# damper.net
KiCad netlist of a schematic drawn in EAGLE
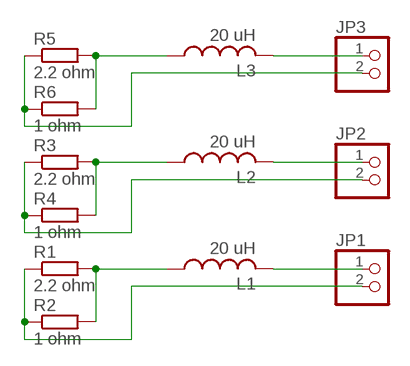
[diagram p0: schematic, sheet 1]

(export (version "E")
  (design (tool "Eeschema 10.0.6"))
  (components
    (comp (ref "JP1")
      (value "PINHD-1X2")
      (footprint "eagle-import:1X02")
      (libsource (lib "eagle-import") (part "PINHD-1X2"))
    )
    (comp (ref "JP2")
      (value "PINHD-1X2")
      (footprint "eagle-import:1X02")
      (libsource (lib "eagle-import") (part "PINHD-1X2"))
    )
    (comp (ref "JP3")
      (value "PINHD-1X2")
      (footprint "eagle-import:1X02")
      (libsource (lib "eagle-import") (part "PINHD-1X2"))
    )
    (comp (ref "L1")
      (value "20 uH")
      (footprint "eagle-import:0207_10")
      (libsource (lib "eagle-import") (part "L-US0207/10"))
    )
    (comp (ref "L2")
      (value "20 uH")
      (footprint "eagle-import:0207_10")
      (libsource (lib "eagle-import") (part "L-US0207/10"))
    )
    (comp (ref "L3")
      (value "20 uH")
      (footprint "eagle-import:0207_10")
      (libsource (lib "eagle-import") (part "L-US0207/10"))
    )
    (comp (ref "R1")
      (value "2.2 ohm")
      (footprint "eagle-import:VTA52")
      (libsource (lib "eagle-import") (part "R-EU_VTA52"))
    )
    (comp (ref "R2")
      (value "1 ohm")
      (footprint "eagle-import:VTA52")
      (libsource (lib "eagle-import") (part "R-EU_VTA52"))
    )
    (comp (ref "R3")
      (value "2.2 ohm")
      (footprint "eagle-import:VTA52")
      (libsource (lib "eagle-import") (part "R-EU_VTA52"))
    )
    (comp (ref "R4")
      (value "1 ohm")
      (footprint "eagle-import:VTA52")
      (libsource (lib "eagle-import") (part "R-EU_VTA52"))
    )
    (comp (ref "R5")
      (value "2.2 ohm")
      (footprint "eagle-import:VTA52")
      (libsource (lib "eagle-import") (part "R-EU_VTA52"))
    )
    (comp (ref "R6")
      (value "1 ohm")
      (footprint "eagle-import:VTA52")
      (libsource (lib "eagle-import") (part "R-EU_VTA52"))
    )
  )
  (nets
    (net (code "1") (name "Net-(JP1-Pad1)") (class "Default")
      (node (ref "JP1") (pin "1") (pinfunction "1_1") (pintype "passive"))
      (node (ref "L1") (pin "2") (pinfunction "2_2") (pintype "passive"))
    )
    (net (code "2") (name "Net-(JP1-Pad2)") (class "Default")
      (node (ref "JP1") (pin "2") (pinfunction "2_2") (pintype "passive"))
      (node (ref "R1") (pin "1") (pinfunction "1_1") (pintype "passive"))
      (node (ref "R2") (pin "1") (pinfunction "1_1") (pintype "passive"))
    )
    (net (code "3") (name "Net-(JP2-Pad1)") (class "Default")
      (node (ref "JP2") (pin "1") (pinfunction "1_1") (pintype "passive"))
      (node (ref "L2") (pin "2") (pinfunction "2_2") (pintype "passive"))
    )
    (net (code "4") (name "Net-(JP2-Pad2)") (class "Default")
      (node (ref "JP2") (pin "2") (pinfunction "2_2") (pintype "passive"))
      (node (ref "R3") (pin "1") (pinfunction "1_1") (pintype "passive"))
      (node (ref "R4") (pin "1") (pinfunction "1_1") (pintype "passive"))
    )
    (net (code "5") (name "Net-(JP3-Pad1)") (class "Default")
      (node (ref "JP3") (pin "1") (pinfunction "1_1") (pintype "passive"))
      (node (ref "L3") (pin "2") (pinfunction "2_2") (pintype "passive"))
    )
    (net (code "6") (name "Net-(JP3-Pad2)") (class "Default")
      (node (ref "JP3") (pin "2") (pinfunction "2_2") (pintype "passive"))
      (node (ref "R5") (pin "1") (pinfunction "1_1") (pintype "passive"))
      (node (ref "R6") (pin "1") (pinfunction "1_1") (pintype "passive"))
    )
    (net (code "7") (name "Net-(L1-Pad1)") (class "Default")
      (node (ref "L1") (pin "1") (pinfunction "1_1") (pintype "passive"))
      (node (ref "R1") (pin "2") (pinfunction "2_2") (pintype "passive"))
      (node (ref "R2") (pin "2") (pinfunction "2_2") (pintype "passive"))
    )
    (net (code "8") (name "Net-(L2-Pad1)") (class "Default")
      (node (ref "L2") (pin "1") (pinfunction "1_1") (pintype "passive"))
      (node (ref "R3") (pin "2") (pinfunction "2_2") (pintype "passive"))
      (node (ref "R4") (pin "2") (pinfunction "2_2") (pintype "passive"))
    )
    (net (code "9") (name "Net-(L3-Pad1)") (class "Default")
      (node (ref "L3") (pin "1") (pinfunction "1_1") (pintype "passive"))
      (node (ref "R5") (pin "2") (pinfunction "2_2") (pintype "passive"))
      (node (ref "R6") (pin "2") (pinfunction "2_2") (pintype "passive"))
    )
  )
)
